# adapter.net
KiCad netlist of a schematic drawn in Altium Designer
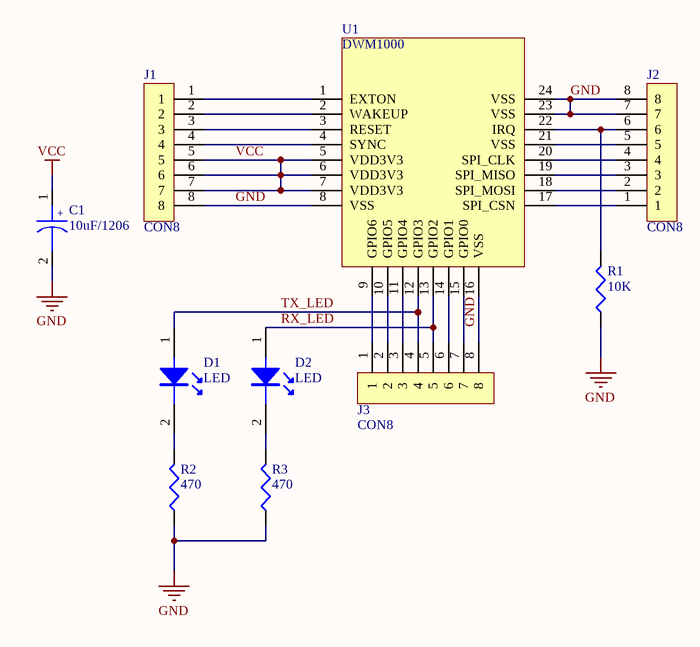
[diagram p0: adapter.SchDoc]

(export (version "E")
  (design (tool "Eeschema 10.0.6"))
  (components
    (comp (ref "C1")
      (value "10uF/1206")
      (footprint "C1206")
      (description "Capacitor")
      (libsource (lib "*") (part "CAP"))
    )
    (comp (ref "D1") (value "LED") (footprint "LED0805") (libsource (lib "*") (part "LED")))
    (comp (ref "D2") (value "LED") (footprint "LED0805") (libsource (lib "*") (part "LED")))
    (comp (ref "J1") (value "CON8") (footprint "HDR1X8") (libsource (lib "") (part "CON8_2")))
    (comp (ref "J2") (value "CON8") (footprint "HDR1X8") (libsource (lib "") (part "CON8_1")))
    (comp (ref "J3") (value "CON8") (footprint "HDR1X8") (libsource (lib "*") (part "CON8")))
    (comp (ref "R1") (value "10K") (footprint "R0603") (libsource (lib "*") (part "RES")))
    (comp (ref "R2") (value "470") (footprint "R0603") (libsource (lib "*") (part "RES")))
    (comp (ref "R3") (value "470") (footprint "R0603") (libsource (lib "*") (part "RES")))
    (comp (ref "U1")
      (value "DWM1000")
      (footprint "DWM1000_MODULE")
      (libsource (lib "*") (part "DWM1000_MODULE"))
    )
  )
  (nets
    (net (code "1") (name "/RX_LED") (class "Default")
      (node (ref "D2") (pin "1") (pinfunction "A_1") (pintype "passive"))
      (node (ref "J3") (pin "5") (pinfunction "5_5") (pintype "passive"))
      (node (ref "U1") (pin "13") (pinfunction "GPIO2_13") (pintype "passive"))
    )
    (net (code "2") (name "/TX_LED") (class "Default")
      (node (ref "D1") (pin "1") (pinfunction "A_1") (pintype "passive"))
      (node (ref "J3") (pin "4") (pinfunction "4_4") (pintype "passive"))
      (node (ref "U1") (pin "12") (pinfunction "GPIO3_12") (pintype "passive"))
    )
    (net (code "3") (name "GND") (class "Default")
      (node (ref "C1") (pin "2") (pinfunction "2_2") (pintype "passive"))
      (node (ref "J1") (pin "8") (pinfunction "8_8") (pintype "passive"))
      (node (ref "J2") (pin "7") (pinfunction "7_7") (pintype "passive"))
      (node (ref "J2") (pin "8") (pinfunction "8_8") (pintype "passive"))
      (node (ref "J3") (pin "8") (pinfunction "8_8") (pintype "passive"))
      (node (ref "R1") (pin "1") (pinfunction "1_1") (pintype "passive"))
      (node (ref "R2") (pin "1") (pinfunction "1_1") (pintype "passive"))
      (node (ref "R3") (pin "1") (pinfunction "1_1") (pintype "passive"))
      (node (ref "U1") (pin "16") (pinfunction "VSS_16") (pintype "passive"))
      (node (ref "U1") (pin "23") (pinfunction "VSS_23") (pintype "passive"))
      (node (ref "U1") (pin "24") (pinfunction "VSS_24") (pintype "passive"))
      (node (ref "U1") (pin "8") (pinfunction "VSS_8") (pintype "passive"))
    )
    (net (code "4") (name "Net-(D1-K)") (class "Default")
      (node (ref "D1") (pin "2") (pinfunction "K_2") (pintype "passive"))
      (node (ref "R2") (pin "2") (pinfunction "2_2") (pintype "passive"))
    )
    (net (code "5") (name "Net-(D2-K)") (class "Default")
      (node (ref "D2") (pin "2") (pinfunction "K_2") (pintype "passive"))
      (node (ref "R3") (pin "2") (pinfunction "2_2") (pintype "passive"))
    )
    (net (code "6") (name "Net-(J2-Pad5)") (class "Default")
      (node (ref "J2") (pin "5") (pinfunction "5_5") (pintype "passive"))
      (node (ref "U1") (pin "21") (pinfunction "VSS_21") (pintype "passive"))
    )
    (net (code "7") (name "Net-(U1-EXTON)") (class "Default")
      (node (ref "J1") (pin "1") (pinfunction "1_1") (pintype "passive"))
      (node (ref "U1") (pin "1") (pinfunction "EXTON_1") (pintype "passive"))
    )
    (net (code "8") (name "Net-(U1-GPIO0)") (class "Default")
      (node (ref "J3") (pin "7") (pinfunction "7_7") (pintype "passive"))
      (node (ref "U1") (pin "15") (pinfunction "GPIO0_15") (pintype "passive"))
    )
    (net (code "9") (name "Net-(U1-GPIO1)") (class "Default")
      (node (ref "J3") (pin "6") (pinfunction "6_6") (pintype "passive"))
      (node (ref "U1") (pin "14") (pinfunction "GPIO1_14") (pintype "passive"))
    )
    (net (code "10") (name "Net-(U1-GPIO4)") (class "Default")
      (node (ref "J3") (pin "3") (pinfunction "3_3") (pintype "passive"))
      (node (ref "U1") (pin "11") (pinfunction "GPIO4_11") (pintype "passive"))
    )
    (net (code "11") (name "Net-(U1-GPIO5)") (class "Default")
      (node (ref "J3") (pin "2") (pinfunction "2_2") (pintype "passive"))
      (node (ref "U1") (pin "10") (pinfunction "GPIO5_10") (pintype "passive"))
    )
    (net (code "12") (name "Net-(U1-GPIO6)") (class "Default")
      (node (ref "J3") (pin "1") (pinfunction "1_1") (pintype "passive"))
      (node (ref "U1") (pin "9") (pinfunction "GPIO6_9") (pintype "passive"))
    )
    (net (code "13") (name "Net-(U1-IRQ)") (class "Default")
      (node (ref "J2") (pin "6") (pinfunction "6_6") (pintype "passive"))
      (node (ref "R1") (pin "2") (pinfunction "2_2") (pintype "passive"))
      (node (ref "U1") (pin "22") (pinfunction "IRQ_22") (pintype "passive"))
    )
    (net (code "14") (name "Net-(U1-RESET)") (class "Default")
      (node (ref "J1") (pin "3") (pinfunction "3_3") (pintype "passive"))
      (node (ref "U1") (pin "3") (pinfunction "RESET_3") (pintype "passive"))
    )
    (net (code "15") (name "Net-(U1-SPI_CLK)") (class "Default")
      (node (ref "J2") (pin "4") (pinfunction "4_4") (pintype "passive"))
      (node (ref "U1") (pin "20") (pinfunction "SPI_CLK_20") (pintype "passive"))
    )
    (net (code "16") (name "Net-(U1-SPI_CSN)") (class "Default")
      (node (ref "J2") (pin "1") (pinfunction "1_1") (pintype "passive"))
      (node (ref "U1") (pin "17") (pinfunction "SPI_CSN_17") (pintype "passive"))
    )
    (net (code "17") (name "Net-(U1-SPI_MISO)") (class "Default")
      (node (ref "J2") (pin "3") (pinfunction "3_3") (pintype "passive"))
      (node (ref "U1") (pin "19") (pinfunction "SPI_MISO_19") (pintype "passive"))
    )
    (net (code "18") (name "Net-(U1-SPI_MOSI)") (class "Default")
      (node (ref "J2") (pin "2") (pinfunction "2_2") (pintype "passive"))
      (node (ref "U1") (pin "18") (pinfunction "SPI_MOSI_18") (pintype "passive"))
    )
    (net (code "19") (name "Net-(U1-SYNC)") (class "Default")
      (node (ref "J1") (pin "4") (pinfunction "4_4") (pintype "passive"))
      (node (ref "U1") (pin "4") (pinfunction "SYNC_4") (pintype "passive"))
    )
    (net (code "20") (name "Net-(U1-WAKEUP)") (class "Default")
      (node (ref "J1") (pin "2") (pinfunction "2_2") (pintype "passive"))
      (node (ref "U1") (pin "2") (pinfunction "WAKEUP_2") (pintype "passive"))
    )
    (net (code "21") (name "VCC") (class "Default")
      (node (ref "C1") (pin "1") (pinfunction "1_1") (pintype "passive"))
      (node (ref "J1") (pin "5") (pinfunction "5_5") (pintype "passive"))
      (node (ref "J1") (pin "6") (pinfunction "6_6") (pintype "passive"))
      (node (ref "J1") (pin "7") (pinfunction "7_7") (pintype "passive"))
      (node (ref "U1") (pin "5") (pinfunction "VDD3V3_5") (pintype "passive"))
      (node (ref "U1") (pin "6") (pinfunction "VDD3V3_6") (pintype "passive"))
      (node (ref "U1") (pin "7") (pinfunction "VDD3V3_7") (pintype "passive"))
    )
  )
)
